# 1_-SODIMM-COL-SOM-iMX8.net
KiCad netlist of a schematic drawn in Altium Designer
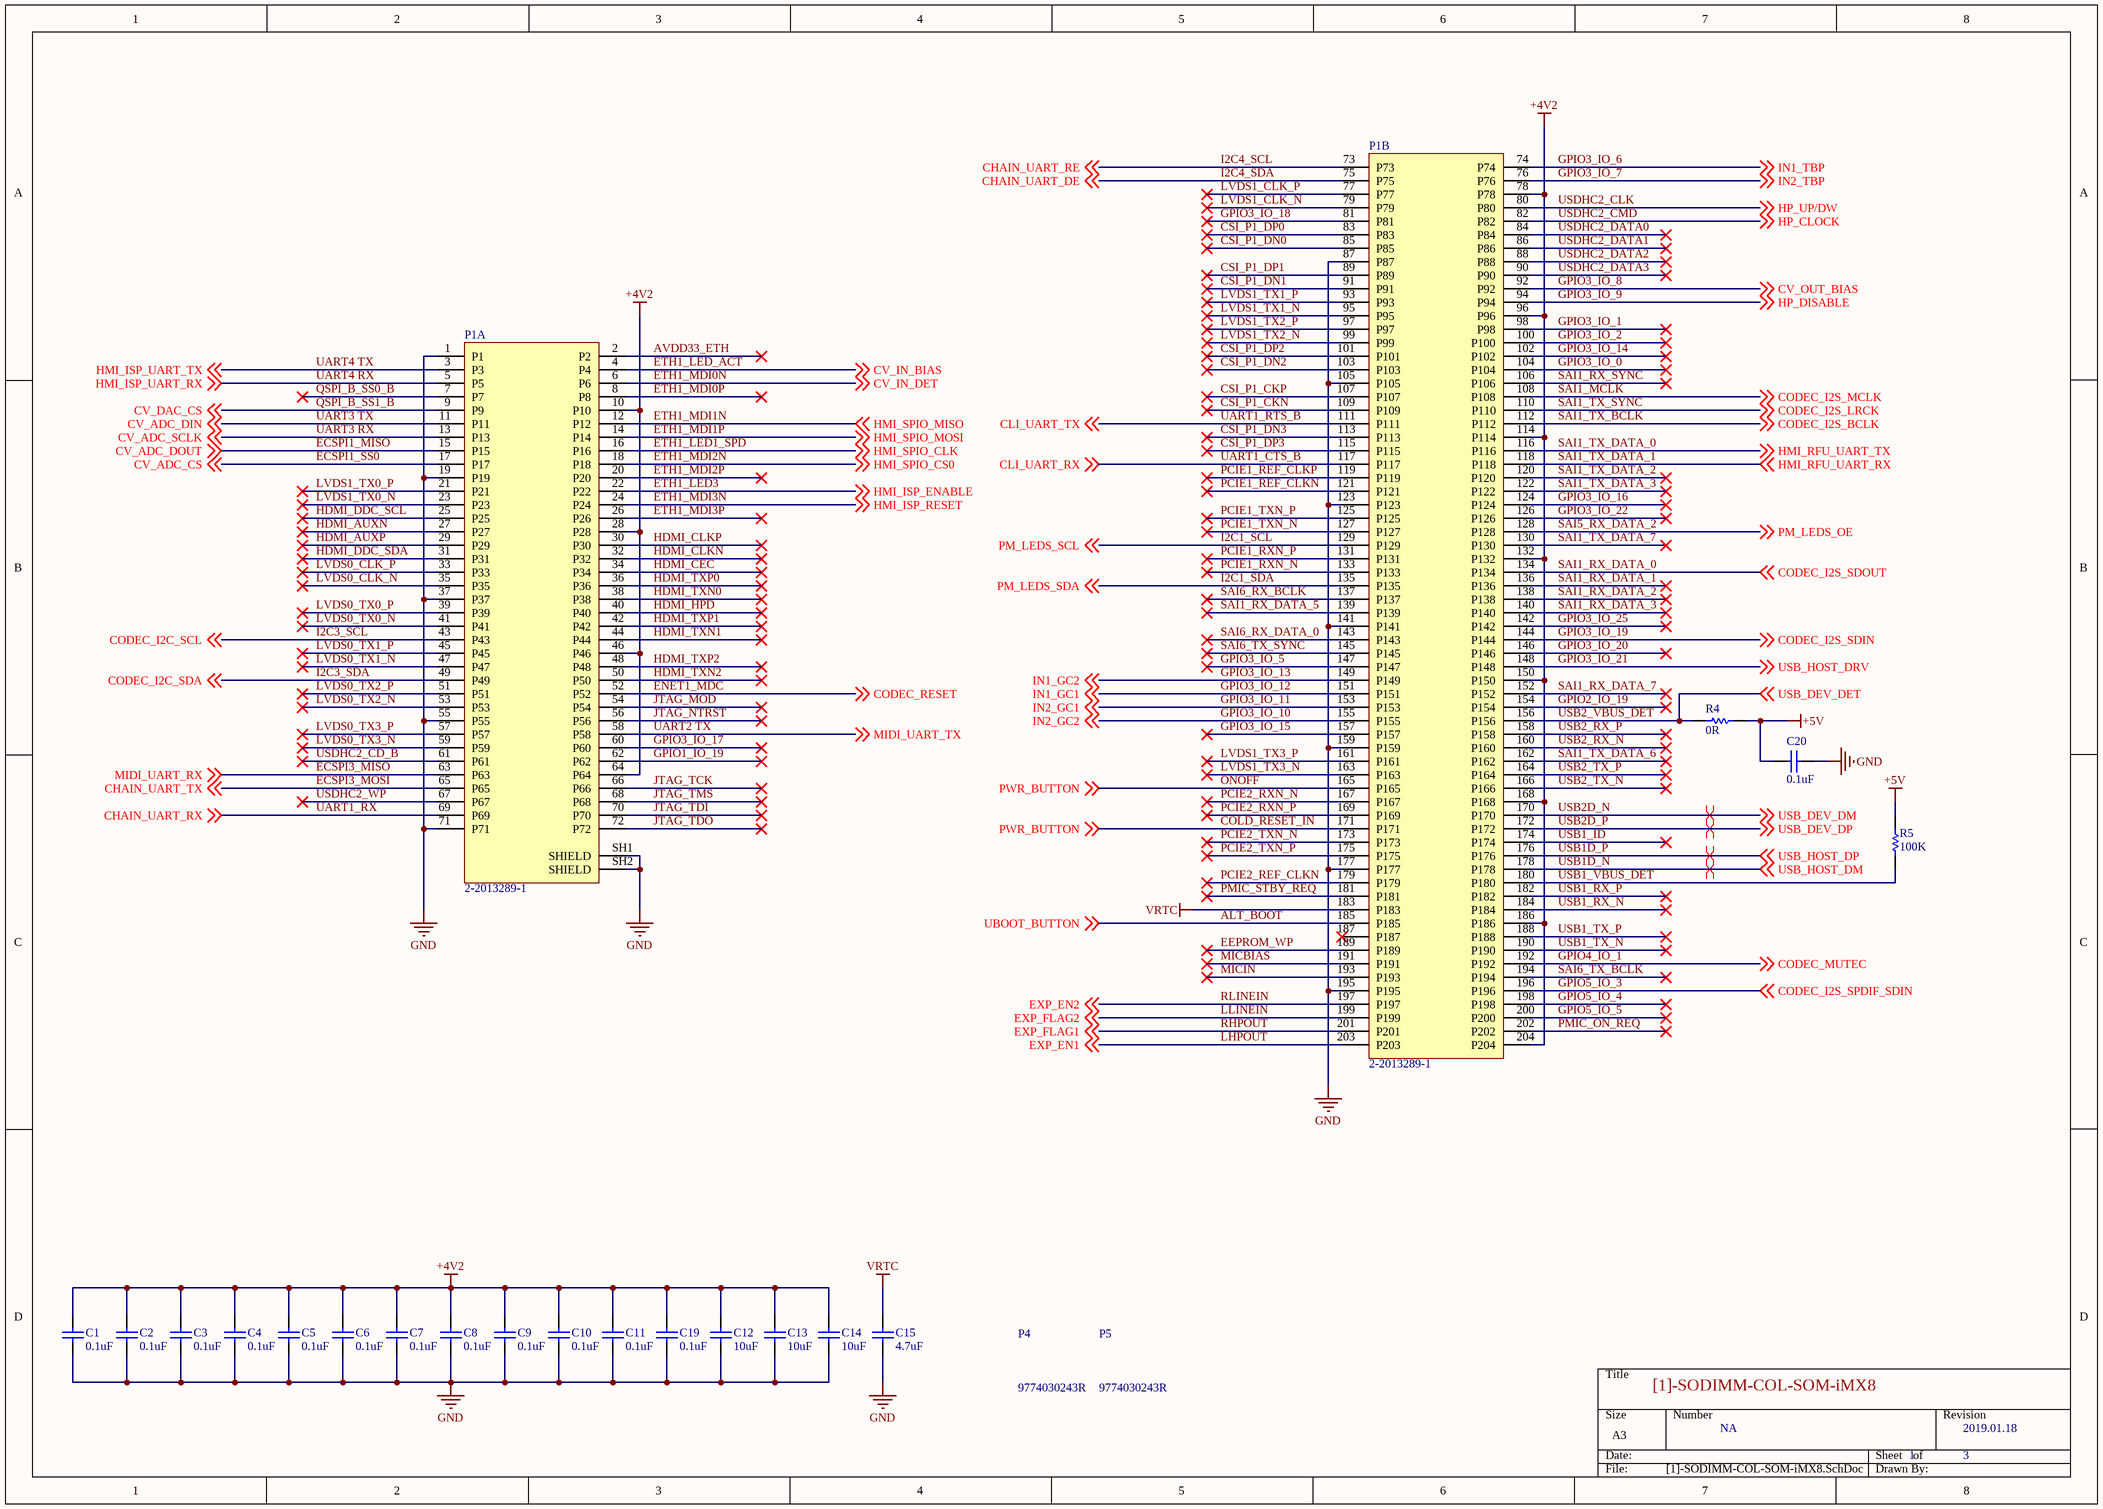
[diagram p0: [1]-SODIMM-COL-SOM-iMX8.SchDoc]

(export (version "E")
  (design (tool "Eeschema 10.0.6"))
  (components
    (comp (ref "C1")
      (value "0.1uF")
      (footprint "CAPC1005N")
      (description "CAP CER 0.1UF 50V X7R 0402")
      (fields (field (name "TOLERANCE") "10 %"))
      (libsource (lib "bitsnio") (part "GRM155R71H104KE14D"))
    )
    (comp (ref "C2")
      (value "0.1uF")
      (footprint "CAPC1005N")
      (description "CAP CER 0.1UF 50V X7R 0402")
      (fields (field (name "TOLERANCE") "10 %"))
      (libsource (lib "bitsnio") (part "GRM155R71H104KE14D"))
    )
    (comp (ref "C3")
      (value "0.1uF")
      (footprint "CAPC1005N")
      (description "CAP CER 0.1UF 50V X7R 0402")
      (fields (field (name "TOLERANCE") "10 %"))
      (libsource (lib "bitsnio") (part "GRM155R71H104KE14D"))
    )
    (comp (ref "C4")
      (value "0.1uF")
      (footprint "CAPC1005N")
      (description "CAP CER 0.1UF 50V X7R 0402")
      (fields (field (name "TOLERANCE") "10 %"))
      (libsource (lib "bitsnio") (part "GRM155R71H104KE14D"))
    )
    (comp (ref "C5")
      (value "0.1uF")
      (footprint "CAPC1005N")
      (description "CAP CER 0.1UF 50V X7R 0402")
      (fields (field (name "TOLERANCE") "10 %"))
      (libsource (lib "bitsnio") (part "GRM155R71H104KE14D"))
    )
    (comp (ref "C6")
      (value "0.1uF")
      (footprint "CAPC1005N")
      (description "CAP CER 0.1UF 50V X7R 0402")
      (fields (field (name "TOLERANCE") "10 %"))
      (libsource (lib "bitsnio") (part "GRM155R71H104KE14D"))
    )
    (comp (ref "C7")
      (value "0.1uF")
      (footprint "CAPC1005N")
      (description "CAP CER 0.1UF 50V X7R 0402")
      (fields (field (name "TOLERANCE") "10 %"))
      (libsource (lib "bitsnio") (part "GRM155R71H104KE14D"))
    )
    (comp (ref "C8")
      (value "0.1uF")
      (footprint "CAPC1005N")
      (description "CAP CER 0.1UF 50V X7R 0402")
      (fields (field (name "TOLERANCE") "10 %"))
      (libsource (lib "bitsnio") (part "GRM155R71H104KE14D"))
    )
    (comp (ref "C9")
      (value "0.1uF")
      (footprint "CAPC1005N")
      (description "CAP CER 0.1UF 50V X7R 0402")
      (fields (field (name "TOLERANCE") "10 %"))
      (libsource (lib "bitsnio") (part "GRM155R71H104KE14D"))
    )
    (comp (ref "C10")
      (value "0.1uF")
      (footprint "CAPC1005N")
      (description "CAP CER 0.1UF 50V X7R 0402")
      (fields (field (name "TOLERANCE") "10 %"))
      (libsource (lib "bitsnio") (part "GRM155R71H104KE14D"))
    )
    (comp (ref "C11")
      (value "0.1uF")
      (footprint "CAPC1005N")
      (description "CAP CER 0.1UF 50V X7R 0402")
      (fields (field (name "TOLERANCE") "10 %"))
      (libsource (lib "bitsnio") (part "GRM155R71H104KE14D"))
    )
    (comp (ref "C12")
      (value "10uF")
      (footprint "CAPC2012N")
      (description "CAP CER 10UF 10V X7R 0805")
      (fields (field (name "TOLERANCE") "10%") (field (name "VOLTAGE") "10V"))
      (libsource (lib "bitsnio") (part "C2012X7R1A106K125AC"))
    )
    (comp (ref "C13")
      (value "10uF")
      (footprint "CAPC2012N")
      (description "CAP CER 10UF 10V X7R 0805")
      (fields (field (name "TOLERANCE") "10%") (field (name "VOLTAGE") "10V"))
      (libsource (lib "bitsnio") (part "C2012X7R1A106K125AC"))
    )
    (comp (ref "C14")
      (value "10uF")
      (footprint "CAPC2012N")
      (description "CAP CER 10UF 10V X7R 0805")
      (fields (field (name "TOLERANCE") "10%") (field (name "VOLTAGE") "10V"))
      (libsource (lib "bitsnio") (part "C2012X7R1A106K125AC"))
    )
    (comp (ref "C15")
      (value "4.7uF")
      (footprint "CAPC1608N")
      (description "CAP CER 4.7UF 10V X5R 0603")
      (fields (field (name "TOLERANCE") "10%"))
      (libsource (lib "bitsnio") (part "LMK107BJ475KAHT"))
    )
    (comp (ref "C19")
      (value "0.1uF")
      (footprint "CAPC1005N")
      (description "CAP CER 0.1UF 50V X7R 0402")
      (fields (field (name "TOLERANCE") "10 %"))
      (libsource (lib "bitsnio") (part "GRM155R71H104KE14D"))
    )
    (comp (ref "C20")
      (value "0.1uF")
      (footprint "CAPC1005N")
      (description "CAP CER 0.1UF 50V X7R 0402")
      (fields (field (name "TOLERANCE") "10 %"))
      (libsource (lib "bitsnio") (part "GRM155R71H104KE14D"))
    )
    (comp (ref "P1")
      (value "2-2013289-1")
      (footprint "TE_2-2013289-1")
      (description "CONN SKT SODIMM 204POS SMD")
      (libsource (lib "bitsnio") (part "2-2013289-1"))
    )
    (comp (ref "P4")
      (value "9774030243R")
      (footprint "9774030243R")
      (description "ROUND STANDOFF M2X0.4 STEEL 3MM")
      (libsource (lib "bitsnio") (part "9774030243R"))
    )
    (comp (ref "P5")
      (value "9774030243R")
      (footprint "9774030243R")
      (description "ROUND STANDOFF M2X0.4 STEEL 3MM")
      (libsource (lib "bitsnio") (part "9774030243R"))
    )
    (comp (ref "R4")
      (value "0R")
      (footprint "RESC1608N")
      (description "RES SMD 0 OHM JUMPER 1/10W 0603")
      (fields
        (field (name "MANUFACTURER") "Panasonic")
        (field (name "MANUFACTURER PART NUMBER") "ERJ-3GEY0R00V")
      )
      (libsource (lib "bitsnio") (part "ERJ-3GEY0R00V"))
    )
    (comp (ref "R5")
      (value "100K")
      (footprint "RESC1005N")
      (description "RES SMD 100K OHM 1% 1/16W 0402")
      (fields (field (name "TOLERANCE") "1 %"))
      (libsource (lib "bitsnio") (part "RC0402FR-07100KL"))
    )
  )
  (nets
    (net (code "1") (name "+4V2") (class "Default")
      (node (ref "C1") (pin "2") (pinfunction "2_2") (pintype "passive"))
      (node (ref "C10") (pin "2") (pinfunction "2_2") (pintype "passive"))
      (node (ref "C11") (pin "2") (pinfunction "2_2") (pintype "passive"))
      (node (ref "C12") (pin "2") (pinfunction "2_2") (pintype "passive"))
      (node (ref "C13") (pin "2") (pinfunction "2_2") (pintype "passive"))
      (node (ref "C14") (pin "2") (pinfunction "2_2") (pintype "passive"))
      (node (ref "C19") (pin "2") (pinfunction "2_2") (pintype "passive"))
      (node (ref "C2") (pin "2") (pinfunction "2_2") (pintype "passive"))
      (node (ref "C3") (pin "2") (pinfunction "2_2") (pintype "passive"))
      (node (ref "C4") (pin "2") (pinfunction "2_2") (pintype "passive"))
      (node (ref "C5") (pin "2") (pinfunction "2_2") (pintype "passive"))
      (node (ref "C6") (pin "2") (pinfunction "2_2") (pintype "passive"))
      (node (ref "C7") (pin "2") (pinfunction "2_2") (pintype "passive"))
      (node (ref "C8") (pin "2") (pinfunction "2_2") (pintype "passive"))
      (node (ref "C9") (pin "2") (pinfunction "2_2") (pintype "passive"))
      (node (ref "P1") (pin "10") (pinfunction "P10_10") (pintype "passive"))
      (node (ref "P1") (pin "114") (pinfunction "P114_114") (pintype "passive"))
      (node (ref "P1") (pin "132") (pinfunction "P132_132") (pintype "passive"))
      (node (ref "P1") (pin "150") (pinfunction "P150_150") (pintype "passive"))
      (node (ref "P1") (pin "168") (pinfunction "P168_168") (pintype "passive"))
      (node (ref "P1") (pin "186") (pinfunction "P186_186") (pintype "passive"))
      (node (ref "P1") (pin "204") (pinfunction "P204_204") (pintype "passive"))
      (node (ref "P1") (pin "28") (pinfunction "P28_28") (pintype "passive"))
      (node (ref "P1") (pin "46") (pinfunction "P46_46") (pintype "passive"))
      (node (ref "P1") (pin "64") (pinfunction "P64_64") (pintype "passive"))
      (node (ref "P1") (pin "78") (pinfunction "P78_78") (pintype "passive"))
      (node (ref "P1") (pin "96") (pinfunction "P96_96") (pintype "passive"))
    )
    (net (code "2") (name "+5V") (class "Default")
      (node (ref "C20") (pin "2") (pinfunction "2_2") (pintype "passive"))
      (node (ref "R4") (pin "2") (pinfunction "2_2") (pintype "passive"))
      (node (ref "R5") (pin "2") (pinfunction "2_2") (pintype "passive"))
    )
    (net (code "3") (name "/AVDD33_ETH") (class "Default")
      (node (ref "P1") (pin "2") (pinfunction "P2_2") (pintype "passive+no_connect"))
    )
    (net (code "4") (name "/CSI_P1_CKN") (class "Default")
      (node (ref "P1") (pin "109") (pinfunction "P109_109") (pintype "passive+no_connect"))
    )
    (net (code "5") (name "/CSI_P1_CKP") (class "Default")
      (node (ref "P1") (pin "107") (pinfunction "P107_107") (pintype "passive+no_connect"))
    )
    (net (code "6") (name "/CSI_P1_DN0") (class "Default")
      (node (ref "P1") (pin "85") (pinfunction "P85_85") (pintype "passive+no_connect"))
    )
    (net (code "7") (name "/CSI_P1_DN1") (class "Default")
      (node (ref "P1") (pin "91") (pinfunction "P91_91") (pintype "passive+no_connect"))
    )
    (net (code "8") (name "/CSI_P1_DN2") (class "Default")
      (node (ref "P1") (pin "103") (pinfunction "P103_103") (pintype "passive+no_connect"))
    )
    (net (code "9") (name "/CSI_P1_DN3") (class "Default")
      (node (ref "P1") (pin "113") (pinfunction "P113_113") (pintype "passive+no_connect"))
    )
    (net (code "10") (name "/CSI_P1_DP0") (class "Default")
      (node (ref "P1") (pin "83") (pinfunction "P83_83") (pintype "passive+no_connect"))
    )
    (net (code "11") (name "/CSI_P1_DP1") (class "Default")
      (node (ref "P1") (pin "89") (pinfunction "P89_89") (pintype "passive+no_connect"))
    )
    (net (code "12") (name "/CSI_P1_DP2") (class "Default")
      (node (ref "P1") (pin "101") (pinfunction "P101_101") (pintype "passive+no_connect"))
    )
    (net (code "13") (name "/CSI_P1_DP3") (class "Default")
      (node (ref "P1") (pin "115") (pinfunction "P115_115") (pintype "passive+no_connect"))
    )
    (net (code "14") (name "/EEPROM_WP") (class "Default")
      (node (ref "P1") (pin "189") (pinfunction "P189_189") (pintype "passive+no_connect"))
    )
    (net (code "15") (name "/ETH1_MDI0P") (class "Default")
      (node (ref "P1") (pin "8") (pinfunction "P8_8") (pintype "passive+no_connect"))
    )
    (net (code "16") (name "/ETH1_MDI2P") (class "Default")
      (node (ref "P1") (pin "20") (pinfunction "P20_20") (pintype "passive+no_connect"))
    )
    (net (code "17") (name "/ETH1_MDI3P") (class "Default")
      (node (ref "P1") (pin "26") (pinfunction "P26_26") (pintype "passive+no_connect"))
    )
    (net (code "18") (name "/GPIO1_IO_19") (class "Default")
      (node (ref "P1") (pin "62") (pinfunction "P62_62") (pintype "passive+no_connect"))
    )
    (net (code "19") (name "/GPIO2_IO_19") (class "Default")
      (node (ref "P1") (pin "154") (pinfunction "P154_154") (pintype "passive+no_connect"))
    )
    (net (code "20") (name "/GPIO3_IO_0") (class "Default")
      (node (ref "P1") (pin "104") (pinfunction "P104_104") (pintype "passive+no_connect"))
    )
    (net (code "21") (name "/GPIO3_IO_1") (class "Default")
      (node (ref "P1") (pin "98") (pinfunction "P98_98") (pintype "passive+no_connect"))
    )
    (net (code "22") (name "/GPIO3_IO_2") (class "Default")
      (node (ref "P1") (pin "100") (pinfunction "P100_100") (pintype "passive+no_connect"))
    )
    (net (code "23") (name "/GPIO3_IO_5") (class "Default")
      (node (ref "P1") (pin "147") (pinfunction "P147_147") (pintype "passive+no_connect"))
    )
    (net (code "24") (name "/GPIO3_IO_14") (class "Default")
      (node (ref "P1") (pin "102") (pinfunction "P102_102") (pintype "passive+no_connect"))
    )
    (net (code "25") (name "/GPIO3_IO_15") (class "Default")
      (node (ref "P1") (pin "157") (pinfunction "P157_157") (pintype "passive+no_connect"))
    )
    (net (code "26") (name "/GPIO3_IO_16") (class "Default")
      (node (ref "P1") (pin "124") (pinfunction "P124_124") (pintype "passive+no_connect"))
    )
    (net (code "27") (name "/GPIO3_IO_17") (class "Default")
      (node (ref "P1") (pin "60") (pinfunction "P60_60") (pintype "passive+no_connect"))
    )
    (net (code "28") (name "/GPIO3_IO_18") (class "Default")
      (node (ref "P1") (pin "81") (pinfunction "P81_81") (pintype "passive+no_connect"))
    )
    (net (code "29") (name "/GPIO3_IO_20") (class "Default")
      (node (ref "P1") (pin "146") (pinfunction "P146_146") (pintype "passive+no_connect"))
    )
    (net (code "30") (name "/GPIO3_IO_22") (class "Default")
      (node (ref "P1") (pin "126") (pinfunction "P126_126") (pintype "passive+no_connect"))
    )
    (net (code "31") (name "/GPIO3_IO_25") (class "Default")
      (node (ref "P1") (pin "142") (pinfunction "P142_142") (pintype "passive+no_connect"))
    )
    (net (code "32") (name "/GPIO5_IO_4") (class "Default")
      (node (ref "P1") (pin "198") (pinfunction "P198_198") (pintype "passive+no_connect"))
    )
    (net (code "33") (name "/GPIO5_IO_5") (class "Default")
      (node (ref "P1") (pin "200") (pinfunction "P200_200") (pintype "passive+no_connect"))
    )
    (net (code "34") (name "/HDMI_AUXN") (class "Default")
      (node (ref "P1") (pin "27") (pinfunction "P27_27") (pintype "passive+no_connect"))
    )
    (net (code "35") (name "/HDMI_AUXP") (class "Default")
      (node (ref "P1") (pin "29") (pinfunction "P29_29") (pintype "passive+no_connect"))
    )
    (net (code "36") (name "/HDMI_CEC") (class "Default")
      (node (ref "P1") (pin "34") (pinfunction "P34_34") (pintype "passive+no_connect"))
    )
    (net (code "37") (name "/HDMI_CLKN") (class "Default")
      (node (ref "P1") (pin "32") (pinfunction "P32_32") (pintype "passive+no_connect"))
    )
    (net (code "38") (name "/HDMI_CLKP") (class "Default")
      (node (ref "P1") (pin "30") (pinfunction "P30_30") (pintype "passive+no_connect"))
    )
    (net (code "39") (name "/HDMI_DDC_SCL") (class "Default")
      (node (ref "P1") (pin "25") (pinfunction "P25_25") (pintype "passive+no_connect"))
    )
    (net (code "40") (name "/HDMI_DDC_SDA") (class "Default")
      (node (ref "P1") (pin "31") (pinfunction "P31_31") (pintype "passive+no_connect"))
    )
    (net (code "41") (name "/HDMI_HPD") (class "Default")
      (node (ref "P1") (pin "40") (pinfunction "P40_40") (pintype "passive+no_connect"))
    )
    (net (code "42") (name "/HDMI_TXN0") (class "Default")
      (node (ref "P1") (pin "38") (pinfunction "P38_38") (pintype "passive+no_connect"))
    )
    (net (code "43") (name "/HDMI_TXN1") (class "Default")
      (node (ref "P1") (pin "44") (pinfunction "P44_44") (pintype "passive+no_connect"))
    )
    (net (code "44") (name "/HDMI_TXN2") (class "Default")
      (node (ref "P1") (pin "50") (pinfunction "P50_50") (pintype "passive+no_connect"))
    )
    (net (code "45") (name "/HDMI_TXP0") (class "Default")
      (node (ref "P1") (pin "36") (pinfunction "P36_36") (pintype "passive+no_connect"))
    )
    (net (code "46") (name "/HDMI_TXP1") (class "Default")
      (node (ref "P1") (pin "42") (pinfunction "P42_42") (pintype "passive+no_connect"))
    )
    (net (code "47") (name "/HDMI_TXP2") (class "Default")
      (node (ref "P1") (pin "48") (pinfunction "P48_48") (pintype "passive+no_connect"))
    )
    (net (code "48") (name "/JTAG_MOD") (class "Default")
      (node (ref "P1") (pin "54") (pinfunction "P54_54") (pintype "passive+no_connect"))
    )
    (net (code "49") (name "/JTAG_NTRST") (class "Default")
      (node (ref "P1") (pin "56") (pinfunction "P56_56") (pintype "passive+no_connect"))
    )
    (net (code "50") (name "/JTAG_TCK") (class "Default")
      (node (ref "P1") (pin "66") (pinfunction "P66_66") (pintype "passive+no_connect"))
    )
    (net (code "51") (name "/JTAG_TDI") (class "Default")
      (node (ref "P1") (pin "70") (pinfunction "P70_70") (pintype "passive+no_connect"))
    )
    (net (code "52") (name "/JTAG_TDO") (class "Default")
      (node (ref "P1") (pin "72") (pinfunction "P72_72") (pintype "passive+no_connect"))
    )
    (net (code "53") (name "/JTAG_TMS") (class "Default")
      (node (ref "P1") (pin "68") (pinfunction "P68_68") (pintype "passive+no_connect"))
    )
    (net (code "54") (name "/LVDS0_CLK_N") (class "Default")
      (node (ref "P1") (pin "35") (pinfunction "P35_35") (pintype "passive+no_connect"))
    )
    (net (code "55") (name "/LVDS0_CLK_P") (class "Default")
      (node (ref "P1") (pin "33") (pinfunction "P33_33") (pintype "passive+no_connect"))
    )
    (net (code "56") (name "/LVDS0_TX0_N") (class "Default")
      (node (ref "P1") (pin "41") (pinfunction "P41_41") (pintype "passive+no_connect"))
    )
    (net (code "57") (name "/LVDS0_TX0_P") (class "Default")
      (node (ref "P1") (pin "39") (pinfunction "P39_39") (pintype "passive+no_connect"))
    )
    (net (code "58") (name "/LVDS0_TX1_N") (class "Default")
      (node (ref "P1") (pin "47") (pinfunction "P47_47") (pintype "passive+no_connect"))
    )
    (net (code "59") (name "/LVDS0_TX1_P") (class "Default")
      (node (ref "P1") (pin "45") (pinfunction "P45_45") (pintype "passive+no_connect"))
    )
    (net (code "60") (name "/LVDS0_TX2_N") (class "Default")
      (node (ref "P1") (pin "53") (pinfunction "P53_53") (pintype "passive+no_connect"))
    )
    (net (code "61") (name "/LVDS0_TX2_P") (class "Default")
      (node (ref "P1") (pin "51") (pinfunction "P51_51") (pintype "passive+no_connect"))
    )
    (net (code "62") (name "/LVDS0_TX3_N") (class "Default")
      (node (ref "P1") (pin "59") (pinfunction "P59_59") (pintype "passive+no_connect"))
    )
    (net (code "63") (name "/LVDS0_TX3_P") (class "Default")
      (node (ref "P1") (pin "57") (pinfunction "P57_57") (pintype "passive+no_connect"))
    )
    (net (code "64") (name "/LVDS1_CLK_N") (class "Default")
      (node (ref "P1") (pin "79") (pinfunction "P79_79") (pintype "passive+no_connect"))
    )
    (net (code "65") (name "/LVDS1_CLK_P") (class "Default")
      (node (ref "P1") (pin "77") (pinfunction "P77_77") (pintype "passive+no_connect"))
    )
    (net (code "66") (name "/LVDS1_TX0_N") (class "Default")
      (node (ref "P1") (pin "23") (pinfunction "P23_23") (pintype "passive+no_connect"))
    )
    (net (code "67") (name "/LVDS1_TX0_P") (class "Default")
      (node (ref "P1") (pin "21") (pinfunction "P21_21") (pintype "passive+no_connect"))
    )
    (net (code "68") (name "/LVDS1_TX1_N") (class "Default")
      (node (ref "P1") (pin "95") (pinfunction "P95_95") (pintype "passive+no_connect"))
    )
    (net (code "69") (name "/LVDS1_TX1_P") (class "Default")
      (node (ref "P1") (pin "93") (pinfunction "P93_93") (pintype "passive+no_connect"))
    )
    (net (code "70") (name "/LVDS1_TX2_N") (class "Default")
      (node (ref "P1") (pin "99") (pinfunction "P99_99") (pintype "passive+no_connect"))
    )
    (net (code "71") (name "/LVDS1_TX2_P") (class "Default")
      (node (ref "P1") (pin "97") (pinfunction "P97_97") (pintype "passive+no_connect"))
    )
    (net (code "72") (name "/LVDS1_TX3_N") (class "Default")
      (node (ref "P1") (pin "163") (pinfunction "P163_163") (pintype "passive+no_connect"))
    )
    (net (code "73") (name "/LVDS1_TX3_P") (class "Default")
      (node (ref "P1") (pin "161") (pinfunction "P161_161") (pintype "passive+no_connect"))
    )
    (net (code "74") (name "/MICBIAS") (class "Default")
      (node (ref "P1") (pin "191") (pinfunction "P191_191") (pintype "passive+no_connect"))
    )
    (net (code "75") (name "/MICIN") (class "Default")
      (node (ref "P1") (pin "193") (pinfunction "P193_193") (pintype "passive+no_connect"))
    )
    (net (code "76") (name "/PCIE1_REF_CLKN") (class "Default")
      (node (ref "P1") (pin "121") (pinfunction "P121_121") (pintype "passive+no_connect"))
    )
    (net (code "77") (name "/PCIE1_REF_CLKP") (class "Default")
      (node (ref "P1") (pin "119") (pinfunction "P119_119") (pintype "passive+no_connect"))
    )
    (net (code "78") (name "/PCIE1_RXN_N") (class "Default")
      (node (ref "P1") (pin "133") (pinfunction "P133_133") (pintype "passive+no_connect"))
    )
    (net (code "79") (name "/PCIE1_RXN_P") (class "Default")
      (node (ref "P1") (pin "131") (pinfunction "P131_131") (pintype "passive+no_connect"))
    )
    (net (code "80") (name "/PCIE1_TXN_N") (class "Default")
      (node (ref "P1") (pin "127") (pinfunction "P127_127") (pintype "passive+no_connect"))
    )
    (net (code "81") (name "/PCIE1_TXN_P") (class "Default")
      (node (ref "P1") (pin "125") (pinfunction "P125_125") (pintype "passive+no_connect"))
    )
    (net (code "82") (name "/PCIE2_REF_CLKN") (class "Default")
      (node (ref "P1") (pin "179") (pinfunction "P179_179") (pintype "passive+no_connect"))
    )
    (net (code "83") (name "/PCIE2_RXN_N") (class "Default")
      (node (ref "P1") (pin "167") (pinfunction "P167_167") (pintype "passive+no_connect"))
    )
    (net (code "84") (name "/PCIE2_RXN_P") (class "Default")
      (node (ref "P1") (pin "169") (pinfunction "P169_169") (pintype "passive+no_connect"))
    )
    (net (code "85") (name "/PCIE2_TXN_N") (class "Default")
      (node (ref "P1") (pin "173") (pinfunction "P173_173") (pintype "passive+no_connect"))
    )
    (net (code "86") (name "/PCIE2_TXN_P") (class "Default")
      (node (ref "P1") (pin "175") (pinfunction "P175_175") (pintype "passive+no_connect"))
    )
    (net (code "87") (name "/PMIC_ON_REQ") (class "Default")
      (node (ref "P1") (pin "202") (pinfunction "P202_202") (pintype "passive+no_connect"))
    )
    (net (code "88") (name "/PMIC_STBY_REQ") (class "Default")
      (node (ref "P1") (pin "181") (pinfunction "P181_181") (pintype "passive+no_connect"))
    )
    (net (code "89") (name "/QSPI_B_SS0_B") (class "Default")
      (node (ref "P1") (pin "7") (pinfunction "P7_7") (pintype "passive+no_connect"))
    )
    (net (code "90") (name "/SAI1_RX_DATA_1") (class "Default")
      (node (ref "P1") (pin "136") (pinfunction "P136_136") (pintype "passive+no_connect"))
    )
    (net (code "91") (name "/SAI1_RX_DATA_2") (class "Default")
      (node (ref "P1") (pin "138") (pinfunction "P138_138") (pintype "passive+no_connect"))
    )
    (net (code "92") (name "/SAI1_RX_DATA_3") (class "Default")
      (node (ref "P1") (pin "140") (pinfunction "P140_140") (pintype "passive+no_connect"))
    )
    (net (code "93") (name "/SAI1_RX_DATA_5") (class "Default")
      (node (ref "P1") (pin "139") (pinfunction "P139_139") (pintype "passive+no_connect"))
    )
    (net (code "94") (name "/SAI1_RX_DATA_7") (class "Default")
      (node (ref "P1") (pin "152") (pinfunction "P152_152") (pintype "passive+no_connect"))
    )
    (net (code "95") (name "/SAI1_RX_SYNC") (class "Default")
      (node (ref "P1") (pin "106") (pinfunction "P106_106") (pintype "passive+no_connect"))
    )
    (net (code "96") (name "/SAI1_TX_DATA_2") (class "Default")
      (node (ref "P1") (pin "120") (pinfunction "P120_120") (pintype "passive+no_connect"))
    )
    (net (code "97") (name "/SAI1_TX_DATA_3") (class "Default")
      (node (ref "P1") (pin "122") (pinfunction "P122_122") (pintype "passive+no_connect"))
    )
    (net (code "98") (name "/SAI1_TX_DATA_6") (class "Default")
      (node (ref "P1") (pin "162") (pinfunction "P162_162") (pintype "passive+no_connect"))
    )
    (net (code "99") (name "/SAI1_TX_DATA_7") (class "Default")
      (node (ref "P1") (pin "130") (pinfunction "P130_130") (pintype "passive+no_connect"))
    )
    (net (code "100") (name "/SAI6_RX_BCLK") (class "Default")
      (node (ref "P1") (pin "137") (pinfunction "P137_137") (pintype "passive+no_connect"))
    )
    (net (code "101") (name "/SAI6_RX_DATA_0") (class "Default")
      (node (ref "P1") (pin "143") (pinfunction "P143_143") (pintype "passive+no_connect"))
    )
    (net (code "102") (name "/SAI6_TX_BCLK") (class "Default")
      (node (ref "P1") (pin "194") (pinfunction "P194_194") (pintype "passive+no_connect"))
    )
    (net (code "103") (name "/SAI6_TX_SYNC") (class "Default")
      (node (ref "P1") (pin "145") (pinfunction "P145_145") (pintype "passive+no_connect"))
    )
    (net (code "104") (name "/USB1_ID") (class "Default")
      (node (ref "P1") (pin "174") (pinfunction "P174_174") (pintype "passive+no_connect"))
    )
    (net (code "105") (name "/USB1_RX_N") (class "Default")
      (node (ref "P1") (pin "184") (pinfunction "P184_184") (pintype "passive+no_connect"))
    )
    (net (code "106") (name "/USB1_RX_P") (class "Default")
      (node (ref "P1") (pin "182") (pinfunction "P182_182") (pintype "passive+no_connect"))
    )
    (net (code "107") (name "/USB1_TX_N") (class "Default")
      (node (ref "P1") (pin "190") (pinfunction "P190_190") (pintype "passive+no_connect"))
    )
    (net (code "108") (name "/USB1_TX_P") (class "Default")
      (node (ref "P1") (pin "188") (pinfunction "P188_188") (pintype "passive+no_connect"))
    )
    (net (code "109") (name "/USB1_VBUS_DET") (class "Default")
      (node (ref "P1") (pin "180") (pinfunction "P180_180") (pintype "passive"))
      (node (ref "R5") (pin "1") (pinfunction "1_1") (pintype "passive"))
    )
    (net (code "110") (name "/USB2_RX_N") (class "Default")
      (node (ref "P1") (pin "160") (pinfunction "P160_160") (pintype "passive+no_connect"))
    )
    (net (code "111") (name "/USB2_RX_P") (class "Default")
      (node (ref "P1") (pin "158") (pinfunction "P158_158") (pintype "passive+no_connect"))
    )
    (net (code "112") (name "/USB2_TX_N") (class "Default")
      (node (ref "P1") (pin "166") (pinfunction "P166_166") (pintype "passive+no_connect"))
    )
    (net (code "113") (name "/USB2_TX_P") (class "Default")
      (node (ref "P1") (pin "164") (pinfunction "P164_164") (pintype "passive+no_connect"))
    )
    (net (code "114") (name "/USDHC2_CD_B") (class "Default")
      (node (ref "P1") (pin "61") (pinfunction "P61_61") (pintype "passive+no_connect"))
    )
    (net (code "115") (name "/USDHC2_DATA0") (class "Default")
      (node (ref "P1") (pin "84") (pinfunction "P84_84") (pintype "passive+no_connect"))
    )
    (net (code "116") (name "/USDHC2_DATA1") (class "Default")
      (node (ref "P1") (pin "86") (pinfunction "P86_86") (pintype "passive+no_connect"))
    )
    (net (code "117") (name "/USDHC2_DATA2") (class "Default")
      (node (ref "P1") (pin "88") (pinfunction "P88_88") (pintype "passive+no_connect"))
    )
    (net (code "118") (name "/USDHC2_DATA3") (class "Default")
      (node (ref "P1") (pin "90") (pinfunction "P90_90") (pintype "passive+no_connect"))
    )
    (net (code "119") (name "/USDHC2_WP") (class "Default")
      (node (ref "P1") (pin "67") (pinfunction "P67_67") (pintype "passive+no_connect"))
    )
    (net (code "120") (name "CHAIN_UART_DE") (class "Default")
      (node (ref "P1") (pin "75") (pinfunction "P75_75") (pintype "passive"))
    )
    (net (code "121") (name "CHAIN_UART_RE") (class "Default")
      (node (ref "P1") (pin "73") (pinfunction "P73_73") (pintype "passive"))
    )
    (net (code "122") (name "CHAIN_UART_RX") (class "Default")
      (node (ref "P1") (pin "69") (pinfunction "P69_69") (pintype "passive"))
    )
    (net (code "123") (name "CHAIN_UART_TX") (class "Default")
      (node (ref "P1") (pin "65") (pinfunction "P65_65") (pintype "passive"))
    )
    (net (code "124") (name "CLI_UART_RX") (class "Default")
      (node (ref "P1") (pin "117") (pinfunction "P117_117") (pintype "passive"))
    )
    (net (code "125") (name "CLI_UART_TX") (class "Default")
      (node (ref "P1") (pin "111") (pinfunction "P111_111") (pintype "passive"))
    )
    (net (code "126") (name "CODEC_I2C_SCL") (class "Default")
      (node (ref "P1") (pin "43") (pinfunction "P43_43") (pintype "passive"))
    )
    (net (code "127") (name "CODEC_I2C_SDA") (class "Default")
      (node (ref "P1") (pin "49") (pinfunction "P49_49") (pintype "passive"))
    )
    (net (code "128") (name "CODEC_I2S_BCLK") (class "Default")
      (node (ref "P1") (pin "112") (pinfunction "P112_112") (pintype "passive"))
    )
    (net (code "129") (name "CODEC_I2S_LRCK") (class "Default")
      (node (ref "P1") (pin "110") (pinfunction "P110_110") (pintype "passive"))
    )
    (net (code "130") (name "CODEC_I2S_MCLK") (class "Default")
      (node (ref "P1") (pin "108") (pinfunction "P108_108") (pintype "passive"))
    )
    (net (code "131") (name "CODEC_I2S_SDIN") (class "Default")
      (node (ref "P1") (pin "144") (pinfunction "P144_144") (pintype "passive"))
    )
    (net (code "132") (name "CODEC_I2S_SDOUT") (class "Default")
      (node (ref "P1") (pin "134") (pinfunction "P134_134") (pintype "passive"))
    )
    (net (code "133") (name "CODEC_I2S_SPDIF_SDIN") (class "Default")
      (node (ref "P1") (pin "196") (pinfunction "P196_196") (pintype "passive"))
    )
    (net (code "134") (name "CODEC_MUTEC") (class "Default")
      (node (ref "P1") (pin "192") (pinfunction "P192_192") (pintype "passive"))
    )
    (net (code "135") (name "CODEC_RESET") (class "Default")
      (node (ref "P1") (pin "52") (pinfunction "P52_52") (pintype "passive"))
    )
    (net (code "136") (name "CV_ADC_CS") (class "Default")
      (node (ref "P1") (pin "17") (pinfunction "P17_17") (pintype "passive"))
    )
    (net (code "137") (name "CV_ADC_DIN") (class "Default")
      (node (ref "P1") (pin "11") (pinfunction "P11_11") (pintype "passive"))
    )
    (net (code "138") (name "CV_ADC_DOUT") (class "Default")
      (node (ref "P1") (pin "15") (pinfunction "P15_15") (pintype "passive"))
    )
    (net (code "139") (name "CV_ADC_SCLK") (class "Default")
      (node (ref "P1") (pin "13") (pinfunction "P13_13") (pintype "passive"))
    )
    (net (code "140") (name "CV_DAC_CS") (class "Default")
      (node (ref "P1") (pin "9") (pinfunction "P9_9") (pintype "passive"))
    )
    (net (code "141") (name "CV_IN_BIAS") (class "Default")
      (node (ref "P1") (pin "4") (pinfunction "P4_4") (pintype "passive"))
    )
    (net (code "142") (name "CV_IN_DET") (class "Default")
      (node (ref "P1") (pin "6") (pinfunction "P6_6") (pintype "passive"))
    )
    (net (code "143") (name "CV_OUT_BIAS") (class "Default")
      (node (ref "P1") (pin "92") (pinfunction "P92_92") (pintype "passive"))
    )
    (net (code "144") (name "EXP_EN1") (class "Default")
      (node (ref "P1") (pin "203") (pinfunction "P203_203") (pintype "passive"))
    )
    (net (code "145") (name "EXP_EN2") (class "Default")
      (node (ref "P1") (pin "197") (pinfunction "P197_197") (pintype "passive"))
    )
    (net (code "146") (name "EXP_FLAG1") (class "Default")
      (node (ref "P1") (pin "201") (pinfunction "P201_201") (pintype "passive"))
    )
    (net (code "147") (name "EXP_FLAG2") (class "Default")
      (node (ref "P1") (pin "199") (pinfunction "P199_199") (pintype "passive"))
    )
    (net (code "148") (name "GND") (class "Default")
      (node (ref "C1") (pin "1") (pinfunction "1_1") (pintype "passive"))
      (node (ref "C10") (pin "1") (pinfunction "1_1") (pintype "passive"))
      (node (ref "C11") (pin "1") (pinfunction "1_1") (pintype "passive"))
      (node (ref "C12") (pin "1") (pinfunction "1_1") (pintype "passive"))
      (node (ref "C13") (pin "1") (pinfunction "1_1") (pintype "passive"))
      (node (ref "C14") (pin "1") (pinfunction "1_1") (pintype "passive"))
      (node (ref "C15") (pin "1") (pinfunction "1_1") (pintype "passive"))
      (node (ref "C19") (pin "1") (pinfunction "1_1") (pintype "passive"))
      (node (ref "C2") (pin "1") (pinfunction "1_1") (pintype "passive"))
      (node (ref "C20") (pin "1") (pinfunction "1_1") (pintype "passive"))
      (node (ref "C3") (pin "1") (pinfunction "1_1") (pintype "passive"))
      (node (ref "C4") (pin "1") (pinfunction "1_1") (pintype "passive"))
      (node (ref "C5") (pin "1") (pinfunction "1_1") (pintype "passive"))
      (node (ref "C6") (pin "1") (pinfunction "1_1") (pintype "passive"))
      (node (ref "C7") (pin "1") (pinfunction "1_1") (pintype "passive"))
      (node (ref "C8") (pin "1") (pinfunction "1_1") (pintype "passive"))
      (node (ref "C9") (pin "1") (pinfunction "1_1") (pintype "passive"))
      (node (ref "P1") (pin "1") (pinfunction "P1_1") (pintype "passive"))
      (node (ref "P1") (pin "105") (pinfunction "P105_105") (pintype "passive"))
      (node (ref "P1") (pin "123") (pinfunction "P123_123") (pintype "passive"))
      (node (ref "P1") (pin "141") (pinfunction "P141_141") (pintype "passive"))
      (node (ref "P1") (pin "159") (pinfunction "P159_159") (pintype "passive"))
      (node (ref "P1") (pin "177") (pinfunction "P177_177") (pintype "passive"))
      (node (ref "P1") (pin "19") (pinfunction "P19_19") (pintype "passive"))
      (node (ref "P1") (pin "195") (pinfunction "P195_195") (pintype "passive"))
      (node (ref "P1") (pin "37") (pinfunction "P37_37") (pintype "passive"))
      (node (ref "P1") (pin "55") (pinfunction "P55_55") (pintype "passive"))
      (node (ref "P1") (pin "71") (pinfunction "P71_71") (pintype "passive"))
      (node (ref "P1") (pin "87") (pinfunction "P87_87") (pintype "passive"))
      (node (ref "P1") (pin "SH1") (pinfunction "SHIELD_SH1") (pintype "passive"))
      (node (ref "P1") (pin "SH2") (pinfunction "SHIELD_SH2") (pintype "passive"))
    )
    (net (code "149") (name "HMI_ISP_ENABLE") (class "Default")
      (node (ref "P1") (pin "22") (pinfunction "P22_22") (pintype "passive"))
    )
    (net (code "150") (name "HMI_ISP_RESET") (class "Default")
      (node (ref "P1") (pin "24") (pinfunction "P24_24") (pintype "passive"))
    )
    (net (code "151") (name "HMI_ISP_UART_RX") (class "Default")
      (node (ref "P1") (pin "5") (pinfunction "P5_5") (pintype "passive"))
    )
    (net (code "152") (name "HMI_ISP_UART_TX") (class "Default")
      (node (ref "P1") (pin "3") (pinfunction "P3_3") (pintype "passive"))
    )
    (net (code "153") (name "HMI_RFU_UART_RX") (class "Default")
      (node (ref "P1") (pin "118") (pinfunction "P118_118") (pintype "passive"))
    )
    (net (code "154") (name "HMI_RFU_UART_TX") (class "Default")
      (node (ref "P1") (pin "116") (pinfunction "P116_116") (pintype "passive"))
    )
    (net (code "155") (name "HMI_SPIO_CLK") (class "Default")
      (node (ref "P1") (pin "16") (pinfunction "P16_16") (pintype "passive"))
    )
    (net (code "156") (name "HMI_SPIO_CS0") (class "Default")
      (node (ref "P1") (pin "18") (pinfunction "P18_18") (pintype "passive"))
    )
    (net (code "157") (name "HMI_SPIO_MISO") (class "Default")
      (node (ref "P1") (pin "12") (pinfunction "P12_12") (pintype "passive"))
    )
    (net (code "158") (name "HMI_SPIO_MOSI") (class "Default")
      (node (ref "P1") (pin "14") (pinfunction "P14_14") (pintype "passive"))
    )
    (net (code "159") (name "HP_CLOCK") (class "Default")
      (node (ref "P1") (pin "82") (pinfunction "P82_82") (pintype "passive"))
    )
    (net (code "160") (name "HP_DISABLE") (class "Default")
      (node (ref "P1") (pin "94") (pinfunction "P94_94") (pintype "passive"))
    )
    (net (code "161") (name "HP_UP{slash}DW") (class "Default")
      (node (ref "P1") (pin "80") (pinfunction "P80_80") (pintype "passive"))
    )
    (net (code "162") (name "IN1_GC1") (class "Default")
      (node (ref "P1") (pin "151") (pinfunction "P151_151") (pintype "passive"))
    )
    (net (code "163") (name "IN1_GC2") (class "Default")
      (node (ref "P1") (pin "149") (pinfunction "P149_149") (pintype "passive"))
    )
    (net (code "164") (name "IN1_TBP") (class "Default")
      (node (ref "P1") (pin "74") (pinfunction "P74_74") (pintype "passive"))
    )
    (net (code "165") (name "IN2_GC1") (class "Default")
      (node (ref "P1") (pin "153") (pinfunction "P153_153") (pintype "passive"))
    )
    (net (code "166") (name "IN2_GC2") (class "Default")
      (node (ref "P1") (pin "155") (pinfunction "P155_155") (pintype "passive"))
    )
    (net (code "167") (name "IN2_TBP") (class "Default")
      (node (ref "P1") (pin "76") (pinfunction "P76_76") (pintype "passive"))
    )
    (net (code "168") (name "MIDI_UART_RX") (class "Default")
      (node (ref "P1") (pin "63") (pinfunction "P63_63") (pintype "passive"))
    )
    (net (code "169") (name "MIDI_UART_TX") (class "Default")
      (node (ref "P1") (pin "58") (pinfunction "P58_58") (pintype "passive"))
    )
    (net (code "170") (name "PM_LEDS_OE") (class "Default")
      (node (ref "P1") (pin "128") (pinfunction "P128_128") (pintype "passive"))
    )
    (net (code "171") (name "PM_LEDS_SCL") (class "Default")
      (node (ref "P1") (pin "129") (pinfunction "P129_129") (pintype "passive"))
    )
    (net (code "172") (name "PM_LEDS_SDA") (class "Default")
      (node (ref "P1") (pin "135") (pinfunction "P135_135") (pintype "passive"))
    )
    (net (code "173") (name "PWR_BUTTON") (class "Default")
      (node (ref "P1") (pin "165") (pinfunction "P165_165") (pintype "passive"))
      (node (ref "P1") (pin "171") (pinfunction "P171_171") (pintype "passive"))
    )
    (net (code "174") (name "UBOOT_BUTTON") (class "Default")
      (node (ref "P1") (pin "185") (pinfunction "P185_185") (pintype "passive"))
    )
    (net (code "175") (name "USB_DEV_DET") (class "Default")
      (node (ref "P1") (pin "156") (pinfunction "P156_156") (pintype "passive"))
      (node (ref "R4") (pin "1") (pinfunction "1_1") (pintype "passive"))
    )
    (net (code "176") (name "USB_DEV_DM") (class "Default")
      (node (ref "P1") (pin "170") (pinfunction "P170_170") (pintype "passive"))
    )
    (net (code "177") (name "USB_DEV_DP") (class "Default")
      (node (ref "P1") (pin "172") (pinfunction "P172_172") (pintype "passive"))
    )
    (net (code "178") (name "USB_HOST_DM") (class "Default")
      (node (ref "P1") (pin "178") (pinfunction "P178_178") (pintype "passive"))
    )
    (net (code "179") (name "USB_HOST_DP") (class "Default")
      (node (ref "P1") (pin "176") (pinfunction "P176_176") (pintype "passive"))
    )
    (net (code "180") (name "USB_HOST_DRV") (class "Default")
      (node (ref "P1") (pin "148") (pinfunction "P148_148") (pintype "passive"))
    )
    (net (code "181") (name "VRTC") (class "Default")
      (node (ref "C15") (pin "2") (pinfunction "2_2") (pintype "passive"))
      (node (ref "P1") (pin "183") (pinfunction "P183_183") (pintype "passive"))
    )
    (net (code "182") (name "unconnected-(P1B-P187-Pad187)") (class "Default")
      (node (ref "P1") (pin "187") (pinfunction "P187_187") (pintype "passive+no_connect"))
    )
  )
)
